# 3D-Druck-Platine_v2_0.net
KiCad netlist of a schematic drawn in EAGLE
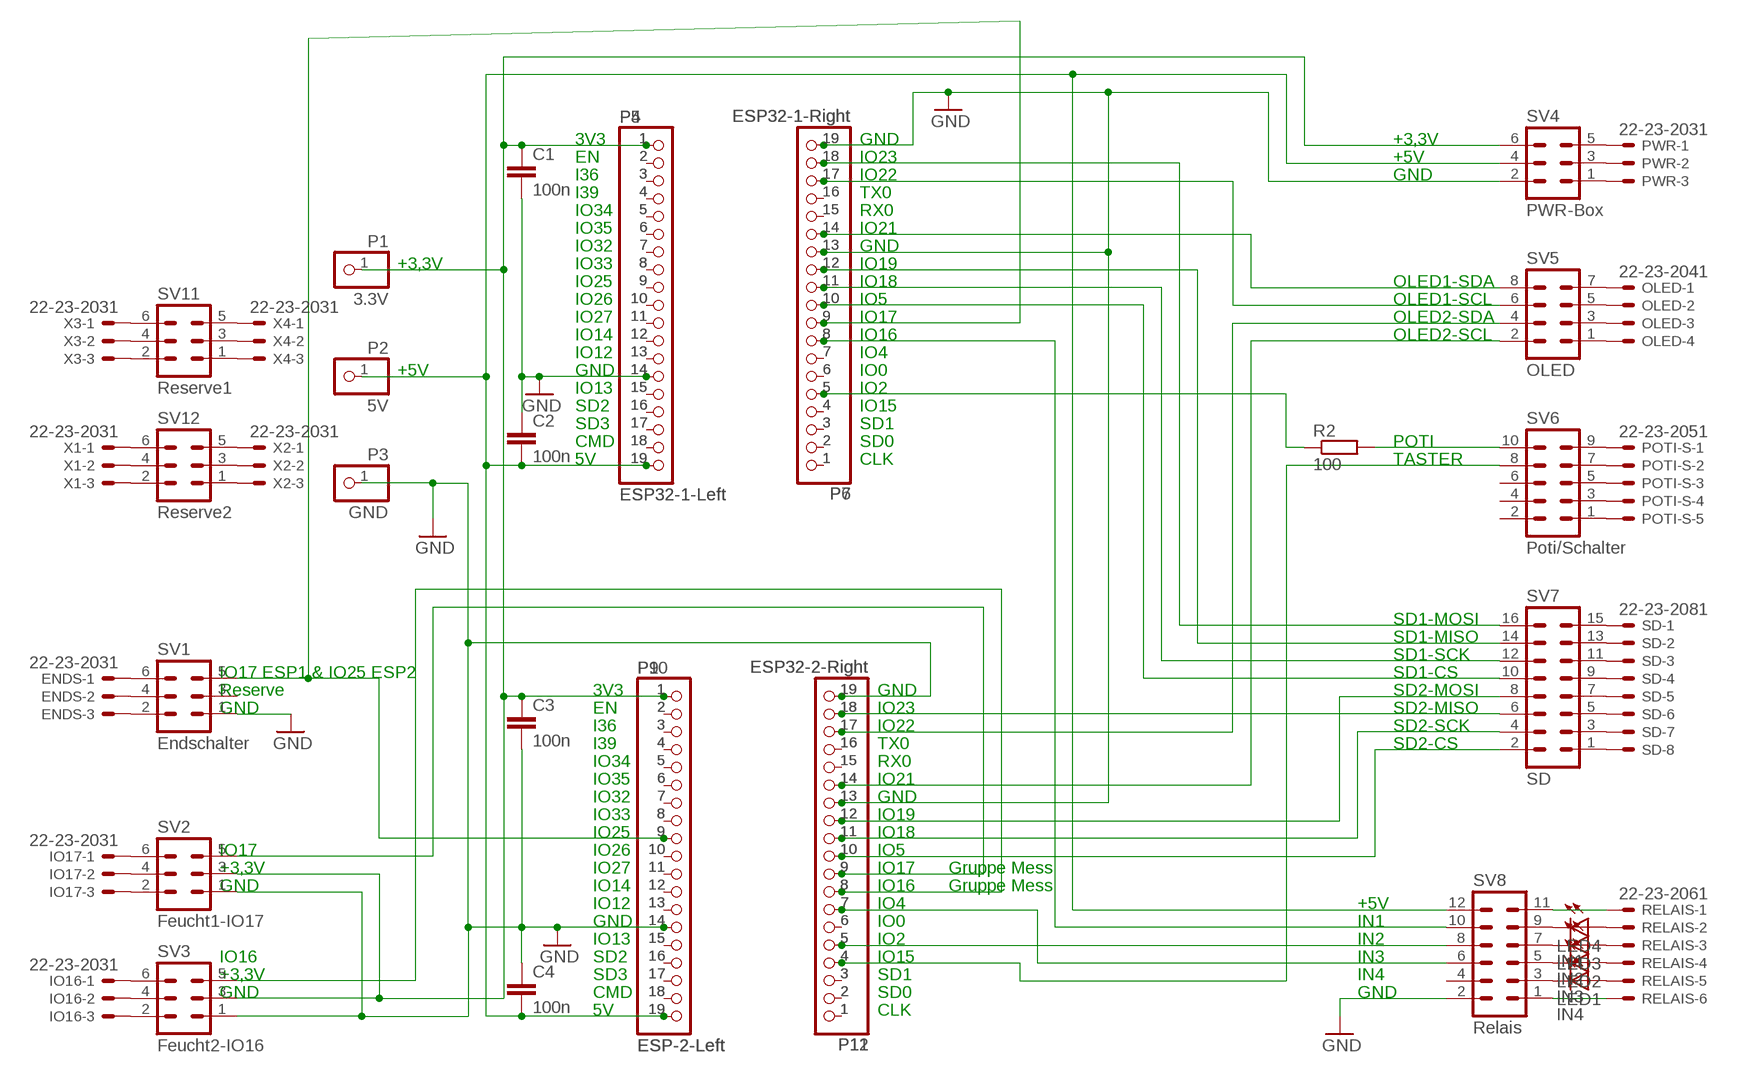
[diagram p0: schematic, sheet 1]

(export (version "E")
  (design (tool "Eeschema 10.0.6"))
  (components
    (comp (ref "C1")
      (value "100n")
      (footprint "eagle-import:C025-024X044")
      (libsource (lib "eagle-import") (part "C-EU025-024X044"))
    )
    (comp (ref "C2")
      (value "100n")
      (footprint "eagle-import:C025-024X044")
      (libsource (lib "eagle-import") (part "C-EU025-024X044"))
    )
    (comp (ref "C3")
      (value "100n")
      (footprint "eagle-import:C025-024X044")
      (libsource (lib "eagle-import") (part "C-EU025-024X044"))
    )
    (comp (ref "C4")
      (value "100n")
      (footprint "eagle-import:C025-024X044")
      (libsource (lib "eagle-import") (part "C-EU025-024X044"))
    )
    (comp (ref "ENDS")
      (value "22-23-2031")
      (footprint "eagle-import:22-23-2031")
      (fields (field (name "MF") "MOLEX"))
      (libsource (lib "eagle-import") (part "22-23-2031"))
    )
    (comp (ref "IO16")
      (value "22-23-2031")
      (footprint "eagle-import:22-23-2031")
      (fields (field (name "MF") "MOLEX"))
      (libsource (lib "eagle-import") (part "22-23-2031"))
    )
    (comp (ref "IO17")
      (value "22-23-2031")
      (footprint "eagle-import:22-23-2031")
      (fields (field (name "MF") "MOLEX"))
      (libsource (lib "eagle-import") (part "22-23-2031"))
    )
    (comp (ref "LED1")
      (value "IN4")
      (footprint "eagle-import:LED3MM")
      (libsource (lib "eagle-import") (part "LED3MM"))
    )
    (comp (ref "LED2")
      (value "IN3")
      (footprint "eagle-import:LED3MM")
      (libsource (lib "eagle-import") (part "LED3MM"))
    )
    (comp (ref "LED3")
      (value "IN2")
      (footprint "eagle-import:LED3MM")
      (libsource (lib "eagle-import") (part "LED3MM"))
    )
    (comp (ref "LED4")
      (value "IN1")
      (footprint "eagle-import:LED3MM")
      (libsource (lib "eagle-import") (part "LED3MM"))
    )
    (comp (ref "OLED")
      (value "22-23-2041")
      (footprint "eagle-import:22-23-2041")
      (fields (field (name "MF") "MOLEX"))
      (libsource (lib "eagle-import") (part "22-23-2041"))
    )
    (comp (ref "P1")
      (value "3.3V")
      (footprint "eagle-import:1X01")
      (libsource (lib "eagle-import") (part "PINHD-1X1"))
    )
    (comp (ref "P2")
      (value "5V")
      (footprint "eagle-import:1X01")
      (libsource (lib "eagle-import") (part "PINHD-1X1"))
    )
    (comp (ref "P3")
      (value "GND")
      (footprint "eagle-import:1X01")
      (libsource (lib "eagle-import") (part "PINHD-1X1"))
    )
    (comp (ref "P4")
      (value "ESP32-1-Left")
      (footprint "eagle-import:1X19")
      (libsource (lib "eagle-import") (part "PINHD-1X19"))
    )
    (comp (ref "P5")
      (value "ESP32-1-Left")
      (footprint "eagle-import:1X19")
      (libsource (lib "eagle-import") (part "PINHD-1X19"))
    )
    (comp (ref "P6")
      (value "ESP32-1-Right")
      (footprint "eagle-import:1X19")
      (libsource (lib "eagle-import") (part "PINHD-1X19"))
    )
    (comp (ref "P7")
      (value "ESP32-1-Right")
      (footprint "eagle-import:1X19")
      (libsource (lib "eagle-import") (part "PINHD-1X19"))
    )
    (comp (ref "P9")
      (value "ESP-2-Left")
      (footprint "eagle-import:1X19")
      (libsource (lib "eagle-import") (part "PINHD-1X19"))
    )
    (comp (ref "P10")
      (value "ESP-2-Left")
      (footprint "eagle-import:1X19")
      (libsource (lib "eagle-import") (part "PINHD-1X19"))
    )
    (comp (ref "P11")
      (value "ESP32-2-Right")
      (footprint "eagle-import:1X19")
      (libsource (lib "eagle-import") (part "PINHD-1X19"))
    )
    (comp (ref "P12")
      (value "ESP32-2-Right")
      (footprint "eagle-import:1X19")
      (libsource (lib "eagle-import") (part "PINHD-1X19"))
    )
    (comp (ref "POTI-S")
      (value "22-23-2051")
      (footprint "eagle-import:22-23-2051")
      (fields (field (name "MF") "MOLEX"))
      (libsource (lib "eagle-import") (part "22-23-2051"))
    )
    (comp (ref "PWR")
      (value "22-23-2031")
      (footprint "eagle-import:22-23-2031")
      (fields (field (name "MF") "MOLEX"))
      (libsource (lib "eagle-import") (part "22-23-2031"))
    )
    (comp (ref "R2")
      (value "100")
      (footprint "eagle-import:0207_10")
      (libsource (lib "eagle-import") (part "R-EU_0207/10"))
    )
    (comp (ref "RELAIS")
      (value "22-23-2061")
      (footprint "eagle-import:22-23-2061")
      (fields (field (name "MF") "MOLEX"))
      (libsource (lib "eagle-import") (part "22-23-2061"))
    )
    (comp (ref "SD")
      (value "22-23-2081")
      (footprint "eagle-import:22-23-2081")
      (fields (field (name "MF") "MOLEX"))
      (libsource (lib "eagle-import") (part "22-23-2081"))
    )
    (comp (ref "SV1")
      (value "Endschalter")
      (footprint "eagle-import:MA03-2")
      (libsource (lib "eagle-import") (part "MA03-2"))
    )
    (comp (ref "SV2")
      (value "Feucht1-IO17")
      (footprint "eagle-import:MA03-2")
      (libsource (lib "eagle-import") (part "MA03-2"))
    )
    (comp (ref "SV3")
      (value "Feucht2-IO16")
      (footprint "eagle-import:MA03-2")
      (libsource (lib "eagle-import") (part "MA03-2"))
    )
    (comp (ref "SV4")
      (value "PWR-Box")
      (footprint "eagle-import:MA03-2")
      (libsource (lib "eagle-import") (part "MA03-2"))
    )
    (comp (ref "SV5")
      (value "OLED")
      (footprint "eagle-import:MA04-2")
      (libsource (lib "eagle-import") (part "MA04-2"))
    )
    (comp (ref "SV6")
      (value "Poti/Schalter")
      (footprint "eagle-import:MA05-2")
      (libsource (lib "eagle-import") (part "MA05-2"))
    )
    (comp (ref "SV7")
      (value "SD")
      (footprint "eagle-import:MA08-2")
      (libsource (lib "eagle-import") (part "MA08-2"))
    )
    (comp (ref "SV8")
      (value "Relais")
      (footprint "eagle-import:MA06-2")
      (libsource (lib "eagle-import") (part "MA06-2"))
    )
    (comp (ref "SV11")
      (value "Reserve1")
      (footprint "eagle-import:MA03-2")
      (libsource (lib "eagle-import") (part "MA03-2"))
    )
    (comp (ref "SV12")
      (value "Reserve2")
      (footprint "eagle-import:MA03-2")
      (libsource (lib "eagle-import") (part "MA03-2"))
    )
    (comp (ref "X1")
      (value "22-23-2031")
      (footprint "eagle-import:22-23-2031")
      (fields (field (name "MF") "MOLEX"))
      (libsource (lib "eagle-import") (part "22-23-2031"))
    )
    (comp (ref "X2")
      (value "22-23-2031")
      (footprint "eagle-import:22-23-2031")
      (fields (field (name "MF") "MOLEX"))
      (libsource (lib "eagle-import") (part "22-23-2031"))
    )
    (comp (ref "X3")
      (value "22-23-2031")
      (footprint "eagle-import:22-23-2031")
      (fields (field (name "MF") "MOLEX"))
      (libsource (lib "eagle-import") (part "22-23-2031"))
    )
    (comp (ref "X4")
      (value "22-23-2031")
      (footprint "eagle-import:22-23-2031")
      (fields (field (name "MF") "MOLEX"))
      (libsource (lib "eagle-import") (part "22-23-2031"))
    )
  )
  (nets
    (net (code "1") (name "GND") (class "Default")
      (node (ref "C1") (pin "2") (pinfunction "2_2") (pintype "passive"))
      (node (ref "C2") (pin "1") (pinfunction "1_1") (pintype "passive"))
      (node (ref "C3") (pin "2") (pinfunction "2_2") (pintype "passive"))
      (node (ref "C4") (pin "1") (pinfunction "1_1") (pintype "passive"))
      (node (ref "P10") (pin "14") (pinfunction "14_14") (pintype "passive"))
      (node (ref "P11") (pin "13") (pinfunction "13_13") (pintype "passive"))
      (node (ref "P11") (pin "19") (pinfunction "19_19") (pintype "passive"))
      (node (ref "P12") (pin "13") (pinfunction "13_13") (pintype "passive"))
      (node (ref "P12") (pin "19") (pinfunction "19_19") (pintype "passive"))
      (node (ref "P3") (pin "1") (pinfunction "1_1") (pintype "passive"))
      (node (ref "P4") (pin "14") (pinfunction "14_14") (pintype "passive"))
      (node (ref "P5") (pin "14") (pinfunction "14_14") (pintype "passive"))
      (node (ref "P6") (pin "13") (pinfunction "13_13") (pintype "passive"))
      (node (ref "P6") (pin "19") (pinfunction "19_19") (pintype "passive"))
      (node (ref "P7") (pin "13") (pinfunction "13_13") (pintype "passive"))
      (node (ref "P7") (pin "19") (pinfunction "19_19") (pintype "passive"))
      (node (ref "P9") (pin "14") (pinfunction "14_14") (pintype "passive"))
      (node (ref "SV1") (pin "1") (pinfunction "1_1") (pintype "passive"))
      (node (ref "SV2") (pin "1") (pinfunction "1_1") (pintype "passive"))
      (node (ref "SV3") (pin "1") (pinfunction "1_1") (pintype "passive"))
      (node (ref "SV4") (pin "2") (pinfunction "2_2") (pintype "passive"))
      (node (ref "SV8") (pin "2") (pinfunction "2_2") (pintype "passive"))
    )
    (net (code "2") (name "Net-(C1-Pad1)") (class "Default")
      (node (ref "C1") (pin "1") (pinfunction "1_1") (pintype "passive"))
      (node (ref "C3") (pin "1") (pinfunction "1_1") (pintype "passive"))
      (node (ref "P1") (pin "1") (pinfunction "1_1") (pintype "passive"))
      (node (ref "P10") (pin "1") (pinfunction "1_1") (pintype "passive"))
      (node (ref "P4") (pin "1") (pinfunction "1_1") (pintype "passive"))
      (node (ref "P5") (pin "1") (pinfunction "1_1") (pintype "passive"))
      (node (ref "P9") (pin "1") (pinfunction "1_1") (pintype "passive"))
      (node (ref "SV2") (pin "3") (pinfunction "3_3") (pintype "passive"))
      (node (ref "SV3") (pin "3") (pinfunction "3_3") (pintype "passive"))
      (node (ref "SV4") (pin "6") (pinfunction "6_6") (pintype "passive"))
    )
    (net (code "3") (name "Net-(C2-Pad2)") (class "Default")
      (node (ref "C2") (pin "2") (pinfunction "2_2") (pintype "passive"))
      (node (ref "C4") (pin "2") (pinfunction "2_2") (pintype "passive"))
      (node (ref "P10") (pin "19") (pinfunction "19_19") (pintype "passive"))
      (node (ref "P2") (pin "1") (pinfunction "1_1") (pintype "passive"))
      (node (ref "P4") (pin "19") (pinfunction "19_19") (pintype "passive"))
      (node (ref "P5") (pin "19") (pinfunction "19_19") (pintype "passive"))
      (node (ref "P9") (pin "19") (pinfunction "19_19") (pintype "passive"))
      (node (ref "SV4") (pin "4") (pinfunction "4_4") (pintype "passive"))
      (node (ref "SV8") (pin "12") (pinfunction "12_12") (pintype "passive"))
    )
    (net (code "4") (name "Net-(ENDSA-S)") (class "Default")
      (node (ref "ENDS") (pin "1") (pinfunction "S_1") (pintype "passive"))
      (node (ref "SV1") (pin "6") (pinfunction "6_6") (pintype "passive"))
    )
    (net (code "5") (name "Net-(ENDSB-S)") (class "Default")
      (node (ref "ENDS") (pin "2") (pinfunction "S_2") (pintype "passive"))
      (node (ref "SV1") (pin "4") (pinfunction "4_4") (pintype "passive"))
    )
    (net (code "6") (name "Net-(ENDSC-S)") (class "Default")
      (node (ref "ENDS") (pin "3") (pinfunction "S_3") (pintype "passive"))
      (node (ref "SV1") (pin "2") (pinfunction "2_2") (pintype "passive"))
    )
    (net (code "7") (name "Net-(IO16A-S)") (class "Default")
      (node (ref "IO16") (pin "1") (pinfunction "S_1") (pintype "passive"))
      (node (ref "SV3") (pin "6") (pinfunction "6_6") (pintype "passive"))
    )
    (net (code "8") (name "Net-(IO16B-S)") (class "Default")
      (node (ref "IO16") (pin "2") (pinfunction "S_2") (pintype "passive"))
      (node (ref "SV3") (pin "4") (pinfunction "4_4") (pintype "passive"))
    )
    (net (code "9") (name "Net-(IO16C-S)") (class "Default")
      (node (ref "IO16") (pin "3") (pinfunction "S_3") (pintype "passive"))
      (node (ref "SV3") (pin "2") (pinfunction "2_2") (pintype "passive"))
    )
    (net (code "10") (name "Net-(IO17A-S)") (class "Default")
      (node (ref "IO17") (pin "1") (pinfunction "S_1") (pintype "passive"))
      (node (ref "SV2") (pin "6") (pinfunction "6_6") (pintype "passive"))
    )
    (net (code "11") (name "Net-(IO17B-S)") (class "Default")
      (node (ref "IO17") (pin "2") (pinfunction "S_2") (pintype "passive"))
      (node (ref "SV2") (pin "4") (pinfunction "4_4") (pintype "passive"))
    )
    (net (code "12") (name "Net-(IO17C-S)") (class "Default")
      (node (ref "IO17") (pin "3") (pinfunction "S_3") (pintype "passive"))
      (node (ref "SV2") (pin "2") (pinfunction "2_2") (pintype "passive"))
    )
    (net (code "13") (name "Net-(LED1-C)") (class "Default")
      (node (ref "LED1") (pin "K") (pinfunction "C_K") (pintype "passive"))
      (node (ref "SV8") (pin "3") (pinfunction "3_3") (pintype "passive"))
    )
    (net (code "14") (name "Net-(LED2-C)") (class "Default")
      (node (ref "LED2") (pin "K") (pinfunction "C_K") (pintype "passive"))
      (node (ref "SV8") (pin "5") (pinfunction "5_5") (pintype "passive"))
    )
    (net (code "15") (name "Net-(LED3-C)") (class "Default")
      (node (ref "LED3") (pin "K") (pinfunction "C_K") (pintype "passive"))
      (node (ref "SV8") (pin "7") (pinfunction "7_7") (pintype "passive"))
    )
    (net (code "16") (name "Net-(LED4-C)") (class "Default")
      (node (ref "LED4") (pin "K") (pinfunction "C_K") (pintype "passive"))
      (node (ref "SV8") (pin "9") (pinfunction "9_9") (pintype "passive"))
    )
    (net (code "17") (name "Net-(OLEDA-S)") (class "Default")
      (node (ref "OLED") (pin "1") (pinfunction "S_1") (pintype "passive"))
      (node (ref "SV5") (pin "7") (pinfunction "7_7") (pintype "passive"))
    )
    (net (code "18") (name "Net-(OLEDB-S)") (class "Default")
      (node (ref "OLED") (pin "2") (pinfunction "S_2") (pintype "passive"))
      (node (ref "SV5") (pin "5") (pinfunction "5_5") (pintype "passive"))
    )
    (net (code "19") (name "Net-(OLEDC-S)") (class "Default")
      (node (ref "OLED") (pin "3") (pinfunction "S_3") (pintype "passive"))
      (node (ref "SV5") (pin "3") (pinfunction "3_3") (pintype "passive"))
    )
    (net (code "20") (name "Net-(OLEDD-S)") (class "Default")
      (node (ref "OLED") (pin "4") (pinfunction "S_4") (pintype "passive"))
      (node (ref "SV5") (pin "1") (pinfunction "1_1") (pintype "passive"))
    )
    (net (code "21") (name "Net-(P4-Pad2)") (class "Default")
      (node (ref "P4") (pin "2") (pinfunction "2_2") (pintype "passive"))
      (node (ref "P5") (pin "2") (pinfunction "2_2") (pintype "passive"))
    )
    (net (code "22") (name "Net-(P4-Pad3)") (class "Default")
      (node (ref "P4") (pin "3") (pinfunction "3_3") (pintype "passive"))
      (node (ref "P5") (pin "3") (pinfunction "3_3") (pintype "passive"))
    )
    (net (code "23") (name "Net-(P4-Pad4)") (class "Default")
      (node (ref "P4") (pin "4") (pinfunction "4_4") (pintype "passive"))
      (node (ref "P5") (pin "4") (pinfunction "4_4") (pintype "passive"))
    )
    (net (code "24") (name "Net-(P4-Pad5)") (class "Default")
      (node (ref "P4") (pin "5") (pinfunction "5_5") (pintype "passive"))
      (node (ref "P5") (pin "5") (pinfunction "5_5") (pintype "passive"))
    )
    (net (code "25") (name "Net-(P4-Pad6)") (class "Default")
      (node (ref "P4") (pin "6") (pinfunction "6_6") (pintype "passive"))
      (node (ref "P5") (pin "6") (pinfunction "6_6") (pintype "passive"))
    )
    (net (code "26") (name "Net-(P4-Pad7)") (class "Default")
      (node (ref "P4") (pin "7") (pinfunction "7_7") (pintype "passive"))
      (node (ref "P5") (pin "7") (pinfunction "7_7") (pintype "passive"))
    )
    (net (code "27") (name "Net-(P4-Pad8)") (class "Default")
      (node (ref "P4") (pin "8") (pinfunction "8_8") (pintype "passive"))
      (node (ref "P5") (pin "8") (pinfunction "8_8") (pintype "passive"))
    )
    (net (code "28") (name "Net-(P4-Pad9)") (class "Default")
      (node (ref "P4") (pin "9") (pinfunction "9_9") (pintype "passive"))
      (node (ref "P5") (pin "9") (pinfunction "9_9") (pintype "passive"))
    )
    (net (code "29") (name "Net-(P4-Pad10)") (class "Default")
      (node (ref "P4") (pin "10") (pinfunction "10_10") (pintype "passive"))
      (node (ref "P5") (pin "10") (pinfunction "10_10") (pintype "passive"))
    )
    (net (code "30") (name "Net-(P4-Pad11)") (class "Default")
      (node (ref "P4") (pin "11") (pinfunction "11_11") (pintype "passive"))
      (node (ref "P5") (pin "11") (pinfunction "11_11") (pintype "passive"))
    )
    (net (code "31") (name "Net-(P4-Pad12)") (class "Default")
      (node (ref "P4") (pin "12") (pinfunction "12_12") (pintype "passive"))
      (node (ref "P5") (pin "12") (pinfunction "12_12") (pintype "passive"))
    )
    (net (code "32") (name "Net-(P4-Pad13)") (class "Default")
      (node (ref "P4") (pin "13") (pinfunction "13_13") (pintype "passive"))
      (node (ref "P5") (pin "13") (pinfunction "13_13") (pintype "passive"))
    )
    (net (code "33") (name "Net-(P4-Pad15)") (class "Default")
      (node (ref "P4") (pin "15") (pinfunction "15_15") (pintype "passive"))
      (node (ref "P5") (pin "15") (pinfunction "15_15") (pintype "passive"))
    )
    (net (code "34") (name "Net-(P4-Pad16)") (class "Default")
      (node (ref "P4") (pin "16") (pinfunction "16_16") (pintype "passive"))
      (node (ref "P5") (pin "16") (pinfunction "16_16") (pintype "passive"))
    )
    (net (code "35") (name "Net-(P4-Pad17)") (class "Default")
      (node (ref "P4") (pin "17") (pinfunction "17_17") (pintype "passive"))
      (node (ref "P5") (pin "17") (pinfunction "17_17") (pintype "passive"))
    )
    (net (code "36") (name "Net-(P4-Pad18)") (class "Default")
      (node (ref "P4") (pin "18") (pinfunction "18_18") (pintype "passive"))
      (node (ref "P5") (pin "18") (pinfunction "18_18") (pintype "passive"))
    )
    (net (code "37") (name "Net-(P6-Pad1)") (class "Default")
      (node (ref "P6") (pin "1") (pinfunction "1_1") (pintype "passive"))
      (node (ref "P7") (pin "1") (pinfunction "1_1") (pintype "passive"))
    )
    (net (code "38") (name "Net-(P6-Pad2)") (class "Default")
      (node (ref "P6") (pin "2") (pinfunction "2_2") (pintype "passive"))
      (node (ref "P7") (pin "2") (pinfunction "2_2") (pintype "passive"))
    )
    (net (code "39") (name "Net-(P6-Pad3)") (class "Default")
      (node (ref "P6") (pin "3") (pinfunction "3_3") (pintype "passive"))
      (node (ref "P7") (pin "3") (pinfunction "3_3") (pintype "passive"))
    )
    (net (code "40") (name "Net-(P6-Pad4)") (class "Default")
      (node (ref "P6") (pin "4") (pinfunction "4_4") (pintype "passive"))
      (node (ref "P7") (pin "4") (pinfunction "4_4") (pintype "passive"))
    )
    (net (code "41") (name "Net-(P6-Pad5)") (class "Default")
      (node (ref "P6") (pin "5") (pinfunction "5_5") (pintype "passive"))
      (node (ref "P7") (pin "5") (pinfunction "5_5") (pintype "passive"))
      (node (ref "R2") (pin "1") (pinfunction "1_1") (pintype "passive"))
    )
    (net (code "42") (name "Net-(P6-Pad6)") (class "Default")
      (node (ref "P6") (pin "6") (pinfunction "6_6") (pintype "passive"))
      (node (ref "P7") (pin "6") (pinfunction "6_6") (pintype "passive"))
    )
    (net (code "43") (name "Net-(P6-Pad7)") (class "Default")
      (node (ref "P6") (pin "7") (pinfunction "7_7") (pintype "passive"))
      (node (ref "P7") (pin "7") (pinfunction "7_7") (pintype "passive"))
    )
    (net (code "44") (name "Net-(P6-Pad8)") (class "Default")
      (node (ref "P6") (pin "8") (pinfunction "8_8") (pintype "passive"))
      (node (ref "P7") (pin "8") (pinfunction "8_8") (pintype "passive"))
      (node (ref "SV8") (pin "10") (pinfunction "10_10") (pintype "passive"))
    )
    (net (code "45") (name "Net-(P6-Pad10)") (class "Default")
      (node (ref "P6") (pin "10") (pinfunction "10_10") (pintype "passive"))
      (node (ref "P7") (pin "10") (pinfunction "10_10") (pintype "passive"))
      (node (ref "SV7") (pin "10") (pinfunction "10_10") (pintype "passive"))
    )
    (net (code "46") (name "Net-(P6-Pad11)") (class "Default")
      (node (ref "P6") (pin "11") (pinfunction "11_11") (pintype "passive"))
      (node (ref "P7") (pin "11") (pinfunction "11_11") (pintype "passive"))
      (node (ref "SV7") (pin "12") (pinfunction "12_12") (pintype "passive"))
    )
    (net (code "47") (name "Net-(P6-Pad12)") (class "Default")
      (node (ref "P6") (pin "12") (pinfunction "12_12") (pintype "passive"))
      (node (ref "P7") (pin "12") (pinfunction "12_12") (pintype "passive"))
      (node (ref "SV7") (pin "14") (pinfunction "14_14") (pintype "passive"))
    )
    (net (code "48") (name "Net-(P6-Pad14)") (class "Default")
      (node (ref "P6") (pin "14") (pinfunction "14_14") (pintype "passive"))
      (node (ref "P7") (pin "14") (pinfunction "14_14") (pintype "passive"))
      (node (ref "SV5") (pin "8") (pinfunction "8_8") (pintype "passive"))
    )
    (net (code "49") (name "Net-(P6-Pad15)") (class "Default")
      (node (ref "P6") (pin "15") (pinfunction "15_15") (pintype "passive"))
      (node (ref "P7") (pin "15") (pinfunction "15_15") (pintype "passive"))
    )
    (net (code "50") (name "Net-(P6-Pad16)") (class "Default")
      (node (ref "P6") (pin "16") (pinfunction "16_16") (pintype "passive"))
      (node (ref "P7") (pin "16") (pinfunction "16_16") (pintype "passive"))
    )
    (net (code "51") (name "Net-(P6-Pad17)") (class "Default")
      (node (ref "P6") (pin "17") (pinfunction "17_17") (pintype "passive"))
      (node (ref "P7") (pin "17") (pinfunction "17_17") (pintype "passive"))
      (node (ref "SV5") (pin "6") (pinfunction "6_6") (pintype "passive"))
    )
    (net (code "52") (name "Net-(P6-Pad18)") (class "Default")
      (node (ref "P6") (pin "18") (pinfunction "18_18") (pintype "passive"))
      (node (ref "P7") (pin "18") (pinfunction "18_18") (pintype "passive"))
      (node (ref "SV7") (pin "16") (pinfunction "16_16") (pintype "passive"))
    )
    (net (code "53") (name "Net-(P10-Pad2)") (class "Default")
      (node (ref "P10") (pin "2") (pinfunction "2_2") (pintype "passive"))
      (node (ref "P9") (pin "2") (pinfunction "2_2") (pintype "passive"))
    )
    (net (code "54") (name "Net-(P10-Pad3)") (class "Default")
      (node (ref "P10") (pin "3") (pinfunction "3_3") (pintype "passive"))
      (node (ref "P9") (pin "3") (pinfunction "3_3") (pintype "passive"))
    )
    (net (code "55") (name "Net-(P10-Pad4)") (class "Default")
      (node (ref "P10") (pin "4") (pinfunction "4_4") (pintype "passive"))
      (node (ref "P9") (pin "4") (pinfunction "4_4") (pintype "passive"))
    )
    (net (code "56") (name "Net-(P10-Pad5)") (class "Default")
      (node (ref "P10") (pin "5") (pinfunction "5_5") (pintype "passive"))
      (node (ref "P9") (pin "5") (pinfunction "5_5") (pintype "passive"))
    )
    (net (code "57") (name "Net-(P10-Pad6)") (class "Default")
      (node (ref "P10") (pin "6") (pinfunction "6_6") (pintype "passive"))
      (node (ref "P9") (pin "6") (pinfunction "6_6") (pintype "passive"))
    )
    (net (code "58") (name "Net-(P10-Pad7)") (class "Default")
      (node (ref "P10") (pin "7") (pinfunction "7_7") (pintype "passive"))
      (node (ref "P9") (pin "7") (pinfunction "7_7") (pintype "passive"))
    )
    (net (code "59") (name "Net-(P10-Pad8)") (class "Default")
      (node (ref "P10") (pin "8") (pinfunction "8_8") (pintype "passive"))
      (node (ref "P9") (pin "8") (pinfunction "8_8") (pintype "passive"))
    )
    (net (code "60") (name "Net-(P10-Pad9)") (class "Default")
      (node (ref "P10") (pin "9") (pinfunction "9_9") (pintype "passive"))
      (node (ref "P6") (pin "9") (pinfunction "9_9") (pintype "passive"))
      (node (ref "P7") (pin "9") (pinfunction "9_9") (pintype "passive"))
      (node (ref "P9") (pin "9") (pinfunction "9_9") (pintype "passive"))
      (node (ref "SV1") (pin "5") (pinfunction "5_5") (pintype "passive"))
    )
    (net (code "61") (name "Net-(P10-Pad10)") (class "Default")
      (node (ref "P10") (pin "10") (pinfunction "10_10") (pintype "passive"))
      (node (ref "P9") (pin "10") (pinfunction "10_10") (pintype "passive"))
    )
    (net (code "62") (name "Net-(P10-Pad11)") (class "Default")
      (node (ref "P10") (pin "11") (pinfunction "11_11") (pintype "passive"))
      (node (ref "P9") (pin "11") (pinfunction "11_11") (pintype "passive"))
    )
    (net (code "63") (name "Net-(P10-Pad12)") (class "Default")
      (node (ref "P10") (pin "12") (pinfunction "12_12") (pintype "passive"))
      (node (ref "P9") (pin "12") (pinfunction "12_12") (pintype "passive"))
    )
    (net (code "64") (name "Net-(P10-Pad13)") (class "Default")
      (node (ref "P10") (pin "13") (pinfunction "13_13") (pintype "passive"))
      (node (ref "P9") (pin "13") (pinfunction "13_13") (pintype "passive"))
    )
    (net (code "65") (name "Net-(P10-Pad15)") (class "Default")
      (node (ref "P10") (pin "15") (pinfunction "15_15") (pintype "passive"))
      (node (ref "P9") (pin "15") (pinfunction "15_15") (pintype "passive"))
    )
    (net (code "66") (name "Net-(P10-Pad16)") (class "Default")
      (node (ref "P10") (pin "16") (pinfunction "16_16") (pintype "passive"))
      (node (ref "P9") (pin "16") (pinfunction "16_16") (pintype "passive"))
    )
    (net (code "67") (name "Net-(P10-Pad17)") (class "Default")
      (node (ref "P10") (pin "17") (pinfunction "17_17") (pintype "passive"))
      (node (ref "P9") (pin "17") (pinfunction "17_17") (pintype "passive"))
    )
    (net (code "68") (name "Net-(P10-Pad18)") (class "Default")
      (node (ref "P10") (pin "18") (pinfunction "18_18") (pintype "passive"))
      (node (ref "P9") (pin "18") (pinfunction "18_18") (pintype "passive"))
    )
    (net (code "69") (name "Net-(P11-Pad1)") (class "Default")
      (node (ref "P11") (pin "1") (pinfunction "1_1") (pintype "passive"))
      (node (ref "P12") (pin "1") (pinfunction "1_1") (pintype "passive"))
    )
    (net (code "70") (name "Net-(P11-Pad2)") (class "Default")
      (node (ref "P11") (pin "2") (pinfunction "2_2") (pintype "passive"))
      (node (ref "P12") (pin "2") (pinfunction "2_2") (pintype "passive"))
    )
    (net (code "71") (name "Net-(P11-Pad3)") (class "Default")
      (node (ref "P11") (pin "3") (pinfunction "3_3") (pintype "passive"))
      (node (ref "P12") (pin "3") (pinfunction "3_3") (pintype "passive"))
    )
    (net (code "72") (name "Net-(P11-Pad4)") (class "Default")
      (node (ref "P11") (pin "4") (pinfunction "4_4") (pintype "passive"))
      (node (ref "P12") (pin "4") (pinfunction "4_4") (pintype "passive"))
      (node (ref "SV6") (pin "8") (pinfunction "8_8") (pintype "passive"))
    )
    (net (code "73") (name "Net-(P11-Pad5)") (class "Default")
      (node (ref "P11") (pin "5") (pinfunction "5_5") (pintype "passive"))
      (node (ref "P12") (pin "5") (pinfunction "5_5") (pintype "passive"))
      (node (ref "SV8") (pin "8") (pinfunction "8_8") (pintype "passive"))
    )
    (net (code "74") (name "Net-(P11-Pad6)") (class "Default")
      (node (ref "P11") (pin "6") (pinfunction "6_6") (pintype "passive"))
      (node (ref "P12") (pin "6") (pinfunction "6_6") (pintype "passive"))
    )
    (net (code "75") (name "Net-(P11-Pad7)") (class "Default")
      (node (ref "P11") (pin "7") (pinfunction "7_7") (pintype "passive"))
      (node (ref "P12") (pin "7") (pinfunction "7_7") (pintype "passive"))
      (node (ref "SV8") (pin "6") (pinfunction "6_6") (pintype "passive"))
    )
    (net (code "76") (name "Net-(P11-Pad8)") (class "Default")
      (node (ref "P11") (pin "8") (pinfunction "8_8") (pintype "passive"))
      (node (ref "P12") (pin "8") (pinfunction "8_8") (pintype "passive"))
      (node (ref "SV3") (pin "5") (pinfunction "5_5") (pintype "passive"))
    )
    (net (code "77") (name "Net-(P11-Pad9)") (class "Default")
      (node (ref "P11") (pin "9") (pinfunction "9_9") (pintype "passive"))
      (node (ref "P12") (pin "9") (pinfunction "9_9") (pintype "passive"))
      (node (ref "SV2") (pin "5") (pinfunction "5_5") (pintype "passive"))
    )
    (net (code "78") (name "Net-(P11-Pad10)") (class "Default")
      (node (ref "P11") (pin "10") (pinfunction "10_10") (pintype "passive"))
      (node (ref "P12") (pin "10") (pinfunction "10_10") (pintype "passive"))
      (node (ref "SV7") (pin "2") (pinfunction "2_2") (pintype "passive"))
    )
    (net (code "79") (name "Net-(P11-Pad11)") (class "Default")
      (node (ref "P11") (pin "11") (pinfunction "11_11") (pintype "passive"))
      (node (ref "P12") (pin "11") (pinfunction "11_11") (pintype "passive"))
      (node (ref "SV7") (pin "4") (pinfunction "4_4") (pintype "passive"))
    )
    (net (code "80") (name "Net-(P11-Pad12)") (class "Default")
      (node (ref "P11") (pin "12") (pinfunction "12_12") (pintype "passive"))
      (node (ref "P12") (pin "12") (pinfunction "12_12") (pintype "passive"))
      (node (ref "SV7") (pin "8") (pinfunction "8_8") (pintype "passive"))
    )
    (net (code "81") (name "Net-(P11-Pad14)") (class "Default")
      (node (ref "P11") (pin "14") (pinfunction "14_14") (pintype "passive"))
      (node (ref "P12") (pin "14") (pinfunction "14_14") (pintype "passive"))
      (node (ref "SV5") (pin "2") (pinfunction "2_2") (pintype "passive"))
    )
    (net (code "82") (name "Net-(P11-Pad15)") (class "Default")
      (node (ref "P11") (pin "15") (pinfunction "15_15") (pintype "passive"))
      (node (ref "P12") (pin "15") (pinfunction "15_15") (pintype "passive"))
    )
    (net (code "83") (name "Net-(P11-Pad16)") (class "Default")
      (node (ref "P11") (pin "16") (pinfunction "16_16") (pintype "passive"))
      (node (ref "P12") (pin "16") (pinfunction "16_16") (pintype "passive"))
    )
    (net (code "84") (name "Net-(P11-Pad17)") (class "Default")
      (node (ref "P11") (pin "17") (pinfunction "17_17") (pintype "passive"))
      (node (ref "P12") (pin "17") (pinfunction "17_17") (pintype "passive"))
      (node (ref "SV5") (pin "4") (pinfunction "4_4") (pintype "passive"))
    )
    (net (code "85") (name "Net-(P11-Pad18)") (class "Default")
      (node (ref "P11") (pin "18") (pinfunction "18_18") (pintype "passive"))
      (node (ref "P12") (pin "18") (pinfunction "18_18") (pintype "passive"))
      (node (ref "SV7") (pin "6") (pinfunction "6_6") (pintype "passive"))
    )
    (net (code "86") (name "Net-(POTI-SA-S)") (class "Default")
      (node (ref "POTI-S") (pin "1") (pinfunction "S_1") (pintype "passive"))
      (node (ref "SV6") (pin "9") (pinfunction "9_9") (pintype "passive"))
    )
    (net (code "87") (name "Net-(POTI-SB-S)") (class "Default")
      (node (ref "POTI-S") (pin "2") (pinfunction "S_2") (pintype "passive"))
      (node (ref "SV6") (pin "7") (pinfunction "7_7") (pintype "passive"))
    )
    (net (code "88") (name "Net-(POTI-SC-S)") (class "Default")
      (node (ref "POTI-S") (pin "3") (pinfunction "S_3") (pintype "passive"))
      (node (ref "SV6") (pin "5") (pinfunction "5_5") (pintype "passive"))
    )
    (net (code "89") (name "Net-(POTI-SD-S)") (class "Default")
      (node (ref "POTI-S") (pin "4") (pinfunction "S_4") (pintype "passive"))
      (node (ref "SV6") (pin "3") (pinfunction "3_3") (pintype "passive"))
    )
    (net (code "90") (name "Net-(POTI-SE-S)") (class "Default")
      (node (ref "POTI-S") (pin "5") (pinfunction "S_5") (pintype "passive"))
      (node (ref "SV6") (pin "1") (pinfunction "1_1") (pintype "passive"))
    )
    (net (code "91") (name "Net-(PWRA-S)") (class "Default")
      (node (ref "PWR") (pin "1") (pinfunction "S_1") (pintype "passive"))
      (node (ref "SV4") (pin "5") (pinfunction "5_5") (pintype "passive"))
    )
    (net (code "92") (name "Net-(PWRB-S)") (class "Default")
      (node (ref "PWR") (pin "2") (pinfunction "S_2") (pintype "passive"))
      (node (ref "SV4") (pin "3") (pinfunction "3_3") (pintype "passive"))
    )
    (net (code "93") (name "Net-(PWRC-S)") (class "Default")
      (node (ref "PWR") (pin "3") (pinfunction "S_3") (pintype "passive"))
      (node (ref "SV4") (pin "1") (pinfunction "1_1") (pintype "passive"))
    )
    (net (code "94") (name "Net-(R2-Pad2)") (class "Default")
      (node (ref "R2") (pin "2") (pinfunction "2_2") (pintype "passive"))
      (node (ref "SV6") (pin "10") (pinfunction "10_10") (pintype "passive"))
    )
    (net (code "95") (name "Net-(RELAISA-S)") (class "Default")
      (node (ref "RELAIS") (pin "1") (pinfunction "S_1") (pintype "passive"))
      (node (ref "SV8") (pin "11") (pinfunction "11_11") (pintype "passive"))
    )
    (net (code "96") (name "Net-(RELAISB-S)") (class "Default")
      (node (ref "LED4") (pin "A") (pinfunction "A_A") (pintype "passive"))
      (node (ref "RELAIS") (pin "2") (pinfunction "S_2") (pintype "passive"))
    )
    (net (code "97") (name "Net-(RELAISC-S)") (class "Default")
      (node (ref "LED3") (pin "A") (pinfunction "A_A") (pintype "passive"))
      (node (ref "RELAIS") (pin "3") (pinfunction "S_3") (pintype "passive"))
    )
    (net (code "98") (name "Net-(RELAISD-S)") (class "Default")
      (node (ref "LED2") (pin "A") (pinfunction "A_A") (pintype "passive"))
      (node (ref "RELAIS") (pin "4") (pinfunction "S_4") (pintype "passive"))
    )
    (net (code "99") (name "Net-(RELAISE-S)") (class "Default")
      (node (ref "LED1") (pin "A") (pinfunction "A_A") (pintype "passive"))
      (node (ref "RELAIS") (pin "5") (pinfunction "S_5") (pintype "passive"))
    )
    (net (code "100") (name "Net-(RELAISF-S)") (class "Default")
      (node (ref "RELAIS") (pin "6") (pinfunction "S_6") (pintype "passive"))
      (node (ref "SV8") (pin "1") (pinfunction "1_1") (pintype "passive"))
    )
    (net (code "101") (name "Net-(SDA-S)") (class "Default")
      (node (ref "SD") (pin "1") (pinfunction "S_1") (pintype "passive"))
      (node (ref "SV7") (pin "15") (pinfunction "15_15") (pintype "passive"))
    )
    (net (code "102") (name "Net-(SDB-S)") (class "Default")
      (node (ref "SD") (pin "2") (pinfunction "S_2") (pintype "passive"))
      (node (ref "SV7") (pin "13") (pinfunction "13_13") (pintype "passive"))
    )
    (net (code "103") (name "Net-(SDC-S)") (class "Default")
      (node (ref "SD") (pin "3") (pinfunction "S_3") (pintype "passive"))
      (node (ref "SV7") (pin "11") (pinfunction "11_11") (pintype "passive"))
    )
    (net (code "104") (name "Net-(SDD-S)") (class "Default")
      (node (ref "SD") (pin "4") (pinfunction "S_4") (pintype "passive"))
      (node (ref "SV7") (pin "9") (pinfunction "9_9") (pintype "passive"))
    )
    (net (code "105") (name "Net-(SDE-S)") (class "Default")
      (node (ref "SD") (pin "5") (pinfunction "S_5") (pintype "passive"))
      (node (ref "SV7") (pin "7") (pinfunction "7_7") (pintype "passive"))
    )
    (net (code "106") (name "Net-(SDF-S)") (class "Default")
      (node (ref "SD") (pin "6") (pinfunction "S_6") (pintype "passive"))
      (node (ref "SV7") (pin "5") (pinfunction "5_5") (pintype "passive"))
    )
    (net (code "107") (name "Net-(SDG-S)") (class "Default")
      (node (ref "SD") (pin "7") (pinfunction "S_7") (pintype "passive"))
      (node (ref "SV7") (pin "3") (pinfunction "3_3") (pintype "passive"))
    )
    (net (code "108") (name "Net-(SDH-S)") (class "Default")
      (node (ref "SD") (pin "8") (pinfunction "S_8") (pintype "passive"))
      (node (ref "SV7") (pin "1") (pinfunction "1_1") (pintype "passive"))
    )
    (net (code "109") (name "Net-(X1A-S)") (class "Default")
      (node (ref "SV12") (pin "6") (pinfunction "6_6") (pintype "passive"))
      (node (ref "X1") (pin "1") (pinfunction "S_1") (pintype "passive"))
    )
    (net (code "110") (name "Net-(X1B-S)") (class "Default")
      (node (ref "SV12") (pin "4") (pinfunction "4_4") (pintype "passive"))
      (node (ref "X1") (pin "2") (pinfunction "S_2") (pintype "passive"))
    )
    (net (code "111") (name "Net-(X1C-S)") (class "Default")
      (node (ref "SV12") (pin "2") (pinfunction "2_2") (pintype "passive"))
      (node (ref "X1") (pin "3") (pinfunction "S_3") (pintype "passive"))
    )
    (net (code "112") (name "Net-(X2A-S)") (class "Default")
      (node (ref "SV12") (pin "5") (pinfunction "5_5") (pintype "passive"))
      (node (ref "X2") (pin "1") (pinfunction "S_1") (pintype "passive"))
    )
    (net (code "113") (name "Net-(X2B-S)") (class "Default")
      (node (ref "SV12") (pin "3") (pinfunction "3_3") (pintype "passive"))
      (node (ref "X2") (pin "2") (pinfunction "S_2") (pintype "passive"))
    )
    (net (code "114") (name "Net-(X2C-S)") (class "Default")
      (node (ref "SV12") (pin "1") (pinfunction "1_1") (pintype "passive"))
      (node (ref "X2") (pin "3") (pinfunction "S_3") (pintype "passive"))
    )
    (net (code "115") (name "Net-(X3A-S)") (class "Default")
      (node (ref "SV11") (pin "6") (pinfunction "6_6") (pintype "passive"))
      (node (ref "X3") (pin "1") (pinfunction "S_1") (pintype "passive"))
    )
    (net (code "116") (name "Net-(X3B-S)") (class "Default")
      (node (ref "SV11") (pin "4") (pinfunction "4_4") (pintype "passive"))
      (node (ref "X3") (pin "2") (pinfunction "S_2") (pintype "passive"))
    )
    (net (code "117") (name "Net-(X3C-S)") (class "Default")
      (node (ref "SV11") (pin "2") (pinfunction "2_2") (pintype "passive"))
      (node (ref "X3") (pin "3") (pinfunction "S_3") (pintype "passive"))
    )
    (net (code "118") (name "Net-(X4A-S)") (class "Default")
      (node (ref "SV11") (pin "5") (pinfunction "5_5") (pintype "passive"))
      (node (ref "X4") (pin "1") (pinfunction "S_1") (pintype "passive"))
    )
    (net (code "119") (name "Net-(X4B-S)") (class "Default")
      (node (ref "SV11") (pin "3") (pinfunction "3_3") (pintype "passive"))
      (node (ref "X4") (pin "2") (pinfunction "S_2") (pintype "passive"))
    )
    (net (code "120") (name "Net-(X4C-S)") (class "Default")
      (node (ref "SV11") (pin "1") (pinfunction "1_1") (pintype "passive"))
      (node (ref "X4") (pin "3") (pinfunction "S_3") (pintype "passive"))
    )
    (net (code "121") (name "unconnected-(SV1-Pad3)") (class "Default")
      (node (ref "SV1") (pin "3") (pinfunction "3_3") (pintype "passive"))
    )
    (net (code "122") (name "unconnected-(SV6-Pad2)") (class "Default")
      (node (ref "SV6") (pin "2") (pinfunction "2_2") (pintype "passive"))
    )
    (net (code "123") (name "unconnected-(SV6-Pad4)") (class "Default")
      (node (ref "SV6") (pin "4") (pinfunction "4_4") (pintype "passive"))
    )
    (net (code "124") (name "unconnected-(SV6-Pad6)") (class "Default")
      (node (ref "SV6") (pin "6") (pinfunction "6_6") (pintype "passive"))
    )
    (net (code "125") (name "unconnected-(SV8-Pad4)") (class "Default")
      (node (ref "SV8") (pin "4") (pinfunction "4_4") (pintype "passive"))
    )
  )
)
